# o_power.net
KiCad netlist of a schematic drawn in Altium Designer
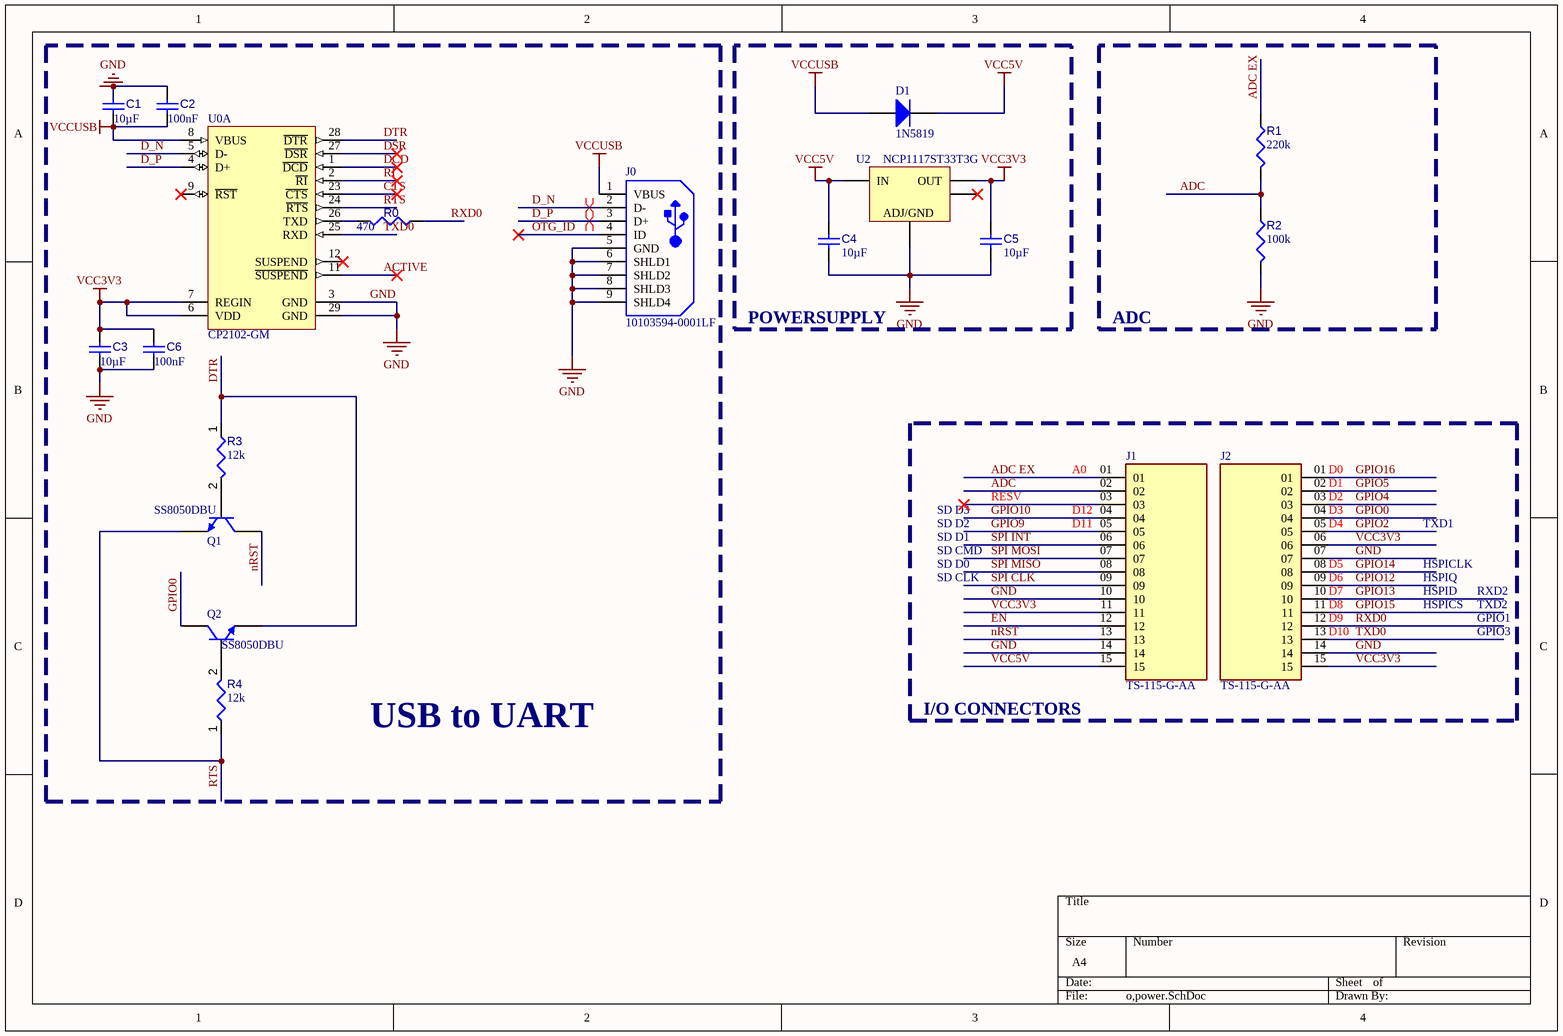
[diagram p0: o,power.SchDoc]

(export (version "E")
  (design (tool "Eeschema 10.0.6"))
  (components
    (comp (ref "C1")
      (value "10µF")
      (footprint "CAPC2013X135X45NL10T25")
      (description "Chip Capacitor, 10 uF, +/- 10%, 16 V, 0805 (2012 Metric)")
      (fields (field (name "TOLERANCE") "10%") (field (name "Comment") "Capacitor 10 uF +/- 10% 16 V 0805"))
      (libsource (lib "Vasavi College of Engineering-Educator Program") (part "CAP-NP-2"))
    )
    (comp (ref "C2")
      (value "100nF")
      (footprint "CAPC2013X95X50LL10T25")
      (description "Chip Capacitor, 100 nF, +/- 10%, 50 V, 0805 (2012 Metric)")
      (fields (field (name "TOLERANCE") "10%") (field (name "Comment") "Capacitor 100 nF +/-10% 50 V 0805"))
      (libsource (lib "Vasavi College of Engineering-Educator Program") (part "CAP-NP-2"))
    )
    (comp (ref "C3")
      (value "10µF")
      (footprint "CAPC2013X135X45NL10T25")
      (description "Chip Capacitor, 10 uF, +/- 10%, 16 V, 0805 (2012 Metric)")
      (fields (field (name "TOLERANCE") "10%") (field (name "Comment") "Capacitor 10 uF +/- 10% 16 V 0805"))
      (libsource (lib "Vasavi College of Engineering-Educator Program") (part "CAP-NP-2"))
    )
    (comp (ref "C4")
      (value "10µF")
      (footprint "CAPC0805(2012)145_L")
      (description "Chip Capacitor, 10µF +/-20%, 25V, 0805, Thickness 1.45 mm")
      (fields (field (name "TOLERANCE") "10%") (field (name "Comment") "Capacitor 10µF +/-20% 25V 0805"))
      (libsource (lib "Vasavi College of Engineering-Educator Program") (part "CAP-NP-2"))
    )
    (comp (ref "C5")
      (value "10µF")
      (footprint "CAPC2013X135X45NL10T25")
      (description "Chip Capacitor, 10 uF, +/- 10%, 16 V, 0805 (2012 Metric)")
      (fields (field (name "TOLERANCE") "10%") (field (name "Comment") "Capacitor 10 uF +/- 10% 16 V 0805"))
      (libsource (lib "Vasavi College of Engineering-Educator Program") (part "CAP-NP-2"))
    )
    (comp (ref "C6")
      (value "100nF")
      (footprint "CAPC2013X95X50LL10T25")
      (description "Chip Capacitor, 100 nF, +/- 10%, 50 V, 0805 (2012 Metric)")
      (fields (field (name "TOLERANCE") "10%") (field (name "Comment") "Capacitor 100 nF +/-10% 50 V 0805"))
      (libsource (lib "Vasavi College of Engineering-Educator Program") (part "CAP-NP-2"))
    )
    (comp (ref "D1")
      (value "1N5819")
      (footprint "ONSC-AXIAL_LEAD-2-59-10_P")
      (description "Low Drop Power Schottky Rectifier, 40 V, 1 A, 2-Pin DO-41, RoHS")
      (fields (field (name "MANUFACTURER") "ON Semiconductor"))
      (libsource (lib "Vasavi College of Engineering-Educator Program") (part "D-AK-2"))
    )
    (comp (ref "J0")
      (value "10103594-0001LF")
      (footprint "FCI-10103594-0001LF_V")
      (description "Micro USB 2.0 B Receptacle, 5 Position, Height 3.24 mm, -55 to 85 degC, RoHS, Tape and Reel")
      (fields (field (name "MANUFACTURER") "FCI Electronics"))
      (libsource (lib "Vasavi College of Engineering-Educator Program") (part "USB-5-6SHLD"))
    )
    (comp (ref "J1")
      (value "TS-115-G-AA")
      (footprint "SAMTEC_TS-115-G-AA")
      (fields (field (name "MF") "Samtec"))
      (libsource (lib "Vasavi College of Engineering-Educator Program") (part "TS-115-G-AA"))
    )
    (comp (ref "J2")
      (value "TS-115-G-AA")
      (footprint "SAMTEC_TS-115-G-AA")
      (fields (field (name "MF") "Samtec"))
      (libsource (lib "") (part "TS-115-G-AA_1"))
    )
    (comp (ref "Q1")
      (value "SS8050DBU")
      (footprint "QFN50P400X400X80_HS-15N")
      (description "Small Signal Bipolar Transistor, 1.5A I(C), 25V V(BR)CEO, 1-Element, NPN, Silicon, TO-92")
      (libsource (lib "Vasavi College of Engineering-Educator Program") (part "TRANS-NPN-3"))
    )
    (comp (ref "Q2")
      (value "SS8050DBU")
      (footprint "QFN50P400X400X80_HS-15N")
      (description "Small Signal Bipolar Transistor, 1.5A I(C), 25V V(BR)CEO, 1-Element, NPN, Silicon, TO-92")
      (libsource (lib "Vasavi College of Engineering-Educator Program") (part "TRANS-NPN-3"))
    )
    (comp (ref "R0")
      (value "470")
      (footprint "RESC0805(2012)_L")
      (description "Chip Resistor, 470 Ohms, +/-5%, 125 mW, -55 to 155 degC, 0805")
      (fields (field (name "TOLERANCE") "5%") (field (name "POWER") "125mW"))
      (libsource (lib "Vasavi College of Engineering-Educator Program") (part "RES-2"))
    )
    (comp (ref "R1")
      (value "220k")
      (footprint "RESC1005X06N")
      (description "Fixed Resistor, Metal Glaze/thick Film, 0.05W, 220000ohm, 25V, 1% +/-Tol, -200,200ppm/Cel, 0201")
      (fields (field (name "POWER") "50mW") (field (name "TOLERANCE") "1%"))
      (libsource (lib "Vasavi College of Engineering-Educator Program") (part "RES-2"))
    )
    (comp (ref "R2")
      (value "100k")
      (footprint "RESC0402(1005)_L")
      (description "Chip Resistor, 100 kOhms, +/-1 %, 63 mW, -55 to 155 degC, 0402")
      (fields (field (name "TOLERANCE") "1%") (field (name "POWER") "63mW"))
      (libsource (lib "Vasavi College of Engineering-Educator Program") (part "RES-2"))
    )
    (comp (ref "R3")
      (value "12k")
      (footprint "RESC0402(1005)_L")
      (description "Chip Resistor, 12 kOhms, +/-1 %, 63 mW, -55 to 155 degC, 0402")
      (fields (field (name "POWER") "63mW") (field (name "TOLERANCE") "1%"))
      (libsource (lib "") (part "RES-2_1"))
    )
    (comp (ref "R4")
      (value "12k")
      (footprint "RESC0402(1005)_L")
      (description "Chip Resistor, 12 kOhms, +/-1 %, 63 mW, -55 to 155 degC, 0402")
      (fields (field (name "POWER") "63mW") (field (name "TOLERANCE") "1%"))
      (libsource (lib "") (part "RES-2_1"))
    )
    (comp (ref "U0")
      (value "CP2102-GM")
      (footprint "BGA81C100P9X9_1100X1100X350")
      (description "USB Bus Controller, CMOS")
      (libsource (lib "Vasavi College of Engineering-Educator Program") (part "SLAB-CP210X-QFN-28-29"))
    )
    (comp (ref "U2")
      (value "NCP1117ST33T3G")
      (footprint "ONSC-SOT-223-4-318H-01_A_V")
      (fields (field (name "MANUFACTURER") "ON Semiconductor"))
      (libsource (lib "Vasavi College of Engineering-Educator Program") (part "ONSC-NCP1117-SOT223-4"))
    )
  )
  (nets
    (net (code "1") (name "/ACTIVE") (class "Default")
      (node (ref "U0") (pin "11") (pinfunction "~{SUSPEND}_11") (pintype "output+no_connect"))
    )
    (net (code "2") (name "/ADC") (class "Default")
      (node (ref "J1") (pin "02") (pinfunction "02_02") (pintype "passive"))
      (node (ref "R1") (pin "2") (pinfunction "2_2") (pintype "passive"))
      (node (ref "R2") (pin "1") (pinfunction "1_1") (pintype "passive"))
    )
    (net (code "3") (name "/ADC EX") (class "Default")
      (node (ref "J1") (pin "01") (pinfunction "01_01") (pintype "passive"))
      (node (ref "R1") (pin "1") (pinfunction "1_1") (pintype "passive"))
    )
    (net (code "4") (name "/CTS") (class "Default")
      (node (ref "U0") (pin "23") (pinfunction "~{CTS}_23") (pintype "input+no_connect"))
    )
    (net (code "5") (name "/DCD") (class "Default")
      (node (ref "U0") (pin "1") (pinfunction "~{DCD}_1") (pintype "input+no_connect"))
    )
    (net (code "6") (name "/DSR") (class "Default")
      (node (ref "U0") (pin "27") (pinfunction "~{DSR}_27") (pintype "input+no_connect"))
    )
    (net (code "7") (name "/DTR") (class "Default")
      (node (ref "Q2") (pin "1") (pinfunction "E_1") (pintype "passive"))
      (node (ref "R3") (pin "1") (pinfunction "1_1") (pintype "passive"))
      (node (ref "U0") (pin "28") (pinfunction "~{DTR}_28") (pintype "output"))
    )
    (net (code "8") (name "/D_N") (class "Default")
      (node (ref "J0") (pin "2") (pinfunction "D-_2") (pintype "passive"))
      (node (ref "U0") (pin "5") (pinfunction "D-_5") (pintype "bidirectional"))
    )
    (net (code "9") (name "/D_P") (class "Default")
      (node (ref "J0") (pin "3") (pinfunction "D+_3") (pintype "passive"))
      (node (ref "U0") (pin "4") (pinfunction "D+_4") (pintype "bidirectional"))
    )
    (net (code "10") (name "/EN") (class "Default")
      (node (ref "J1") (pin "12") (pinfunction "12_12") (pintype "passive"))
    )
    (net (code "11") (name "/GPIO0") (class "Default")
      (node (ref "J2") (pin "04") (pinfunction "04_04") (pintype "passive"))
      (node (ref "Q2") (pin "3") (pinfunction "C_3") (pintype "passive"))
    )
    (net (code "12") (name "/GPIO2") (class "Default")
      (node (ref "J2") (pin "05") (pinfunction "05_05") (pintype "passive"))
    )
    (net (code "13") (name "/GPIO4") (class "Default")
      (node (ref "J2") (pin "03") (pinfunction "03_03") (pintype "passive"))
    )
    (net (code "14") (name "/GPIO5") (class "Default")
      (node (ref "J2") (pin "02") (pinfunction "02_02") (pintype "passive"))
    )
    (net (code "15") (name "/GPIO9") (class "Default")
      (node (ref "J1") (pin "05") (pinfunction "05_05") (pintype "passive"))
    )
    (net (code "16") (name "/GPIO10") (class "Default")
      (node (ref "J1") (pin "04") (pinfunction "04_04") (pintype "passive"))
    )
    (net (code "17") (name "/GPIO12") (class "Default")
      (node (ref "J2") (pin "09") (pinfunction "09_09") (pintype "passive"))
    )
    (net (code "18") (name "/GPIO13") (class "Default")
      (node (ref "J2") (pin "10") (pinfunction "10_10") (pintype "passive"))
    )
    (net (code "19") (name "/GPIO14") (class "Default")
      (node (ref "J2") (pin "08") (pinfunction "08_08") (pintype "passive"))
    )
    (net (code "20") (name "/GPIO15") (class "Default")
      (node (ref "J2") (pin "11") (pinfunction "11_11") (pintype "passive"))
    )
    (net (code "21") (name "/GPIO16") (class "Default")
      (node (ref "J2") (pin "01") (pinfunction "01_01") (pintype "passive"))
    )
    (net (code "22") (name "/OTG_ID") (class "Default")
      (node (ref "J0") (pin "4") (pinfunction "ID_4") (pintype "passive+no_connect"))
    )
    (net (code "23") (name "/RESV") (class "Default")
      (node (ref "J1") (pin "03") (pinfunction "03_03") (pintype "passive+no_connect"))
    )
    (net (code "24") (name "/RI") (class "Default")
      (node (ref "U0") (pin "2") (pinfunction "~{RI}_2") (pintype "input+no_connect"))
    )
    (net (code "25") (name "/RTS") (class "Default")
      (node (ref "Q1") (pin "1") (pinfunction "E_1") (pintype "passive"))
      (node (ref "R4") (pin "1") (pinfunction "1_1") (pintype "passive"))
      (node (ref "U0") (pin "24") (pinfunction "~{RTS}_24") (pintype "output"))
    )
    (net (code "26") (name "/RXD0") (class "Default")
      (node (ref "J2") (pin "12") (pinfunction "12_12") (pintype "passive"))
      (node (ref "R0") (pin "1") (pinfunction "1_1") (pintype "passive"))
    )
    (net (code "27") (name "/SPI CLK") (class "Default")
      (node (ref "J1") (pin "09") (pinfunction "09_09") (pintype "passive"))
    )
    (net (code "28") (name "/SPI INT") (class "Default")
      (node (ref "J1") (pin "06") (pinfunction "06_06") (pintype "passive"))
    )
    (net (code "29") (name "/SPI MISO") (class "Default")
      (node (ref "J1") (pin "08") (pinfunction "08_08") (pintype "passive"))
    )
    (net (code "30") (name "/SPI MOSI") (class "Default")
      (node (ref "J1") (pin "07") (pinfunction "07_07") (pintype "passive"))
    )
    (net (code "31") (name "/TXD0") (class "Default")
      (node (ref "J2") (pin "13") (pinfunction "13_13") (pintype "passive"))
      (node (ref "U0") (pin "25") (pinfunction "RXD_25") (pintype "input"))
    )
    (net (code "32") (name "/nRST") (class "Default")
      (node (ref "J1") (pin "13") (pinfunction "13_13") (pintype "passive"))
      (node (ref "Q1") (pin "3") (pinfunction "C_3") (pintype "passive"))
    )
    (net (code "33") (name "GND") (class "Default")
      (node (ref "C1") (pin "1") (pinfunction "1_1") (pintype "passive"))
      (node (ref "C2") (pin "1") (pinfunction "1_1") (pintype "passive"))
      (node (ref "C3") (pin "2") (pinfunction "2_2") (pintype "passive"))
      (node (ref "C4") (pin "2") (pinfunction "2_2") (pintype "passive"))
      (node (ref "C5") (pin "2") (pinfunction "2_2") (pintype "passive"))
      (node (ref "C6") (pin "2") (pinfunction "2_2") (pintype "passive"))
      (node (ref "J0") (pin "5") (pinfunction "GND_5") (pintype "passive"))
      (node (ref "J0") (pin "6") (pinfunction "SHLD1_6") (pintype "passive"))
      (node (ref "J0") (pin "7") (pinfunction "SHLD2_7") (pintype "passive"))
      (node (ref "J0") (pin "8") (pinfunction "SHLD3_8") (pintype "passive"))
      (node (ref "J0") (pin "9") (pinfunction "SHLD4_9") (pintype "passive"))
      (node (ref "J1") (pin "10") (pinfunction "10_10") (pintype "passive"))
      (node (ref "J1") (pin "14") (pinfunction "14_14") (pintype "passive"))
      (node (ref "J2") (pin "07") (pinfunction "07_07") (pintype "passive"))
      (node (ref "J2") (pin "14") (pinfunction "14_14") (pintype "passive"))
      (node (ref "R2") (pin "2") (pinfunction "2_2") (pintype "passive"))
      (node (ref "U0") (pin "29") (pinfunction "GND_29") (pintype "power_in"))
      (node (ref "U0") (pin "3") (pinfunction "GND_3") (pintype "power_in"))
      (node (ref "U2") (pin "1") (pinfunction "ADJ/GND_1") (pintype "passive"))
    )
    (net (code "34") (name "Net-(Q1-B)") (class "Default")
      (node (ref "Q1") (pin "2") (pinfunction "B_2") (pintype "passive"))
      (node (ref "R3") (pin "2") (pinfunction "2_2") (pintype "passive"))
    )
    (net (code "35") (name "Net-(Q2-B)") (class "Default")
      (node (ref "Q2") (pin "2") (pinfunction "B_2") (pintype "passive"))
      (node (ref "R4") (pin "2") (pinfunction "2_2") (pintype "passive"))
    )
    (net (code "36") (name "Net-(U0A-TXD)") (class "Default")
      (node (ref "R0") (pin "2") (pinfunction "2_2") (pintype "passive"))
      (node (ref "U0") (pin "26") (pinfunction "TXD_26") (pintype "output"))
    )
    (net (code "37") (name "VCC3V3") (class "Default")
      (node (ref "C3") (pin "1") (pinfunction "1_1") (pintype "passive"))
      (node (ref "C5") (pin "1") (pinfunction "1_1") (pintype "passive"))
      (node (ref "C6") (pin "1") (pinfunction "1_1") (pintype "passive"))
      (node (ref "J1") (pin "11") (pinfunction "11_11") (pintype "passive"))
      (node (ref "J2") (pin "06") (pinfunction "06_06") (pintype "passive"))
      (node (ref "J2") (pin "15") (pinfunction "15_15") (pintype "passive"))
      (node (ref "U0") (pin "6") (pinfunction "VDD_6") (pintype "power_in"))
      (node (ref "U0") (pin "7") (pinfunction "REGIN_7") (pintype "power_in"))
      (node (ref "U2") (pin "2") (pinfunction "OUT_2") (pintype "power_in"))
    )
    (net (code "38") (name "VCC5V") (class "Default")
      (node (ref "C4") (pin "1") (pinfunction "1_1") (pintype "passive"))
      (node (ref "D1") (pin "2") (pinfunction "K_2") (pintype "passive"))
      (node (ref "J1") (pin "15") (pinfunction "15_15") (pintype "passive"))
      (node (ref "U2") (pin "3") (pinfunction "IN_3") (pintype "power_in"))
    )
    (net (code "39") (name "VCCUSB") (class "Default")
      (node (ref "C1") (pin "2") (pinfunction "2_2") (pintype "passive"))
      (node (ref "C2") (pin "2") (pinfunction "2_2") (pintype "passive"))
      (node (ref "D1") (pin "1") (pinfunction "A_1") (pintype "passive"))
      (node (ref "J0") (pin "1") (pinfunction "VBUS_1") (pintype "passive"))
      (node (ref "U0") (pin "8") (pinfunction "VBUS_8") (pintype "input"))
    )
    (net (code "40") (name "unconnected-(U0A-SUSPEND-Pad12)") (class "Default")
      (node (ref "U0") (pin "12") (pinfunction "SUSPEND_12") (pintype "output+no_connect"))
    )
    (net (code "41") (name "unconnected-(U0A-~{RST}-Pad9)") (class "Default")
      (node (ref "U0") (pin "9") (pinfunction "~{RST}_9") (pintype "bidirectional+no_connect"))
    )
    (net (code "42") (name "unconnected-(U2-TAB-Pad4)") (class "Default")
      (node (ref "U2") (pin "4") (pinfunction "TAB_4") (pintype "passive+no_connect"))
    )
  )
)
